# Sheet3.net
KiCad netlist of a schematic drawn in Altium Designer
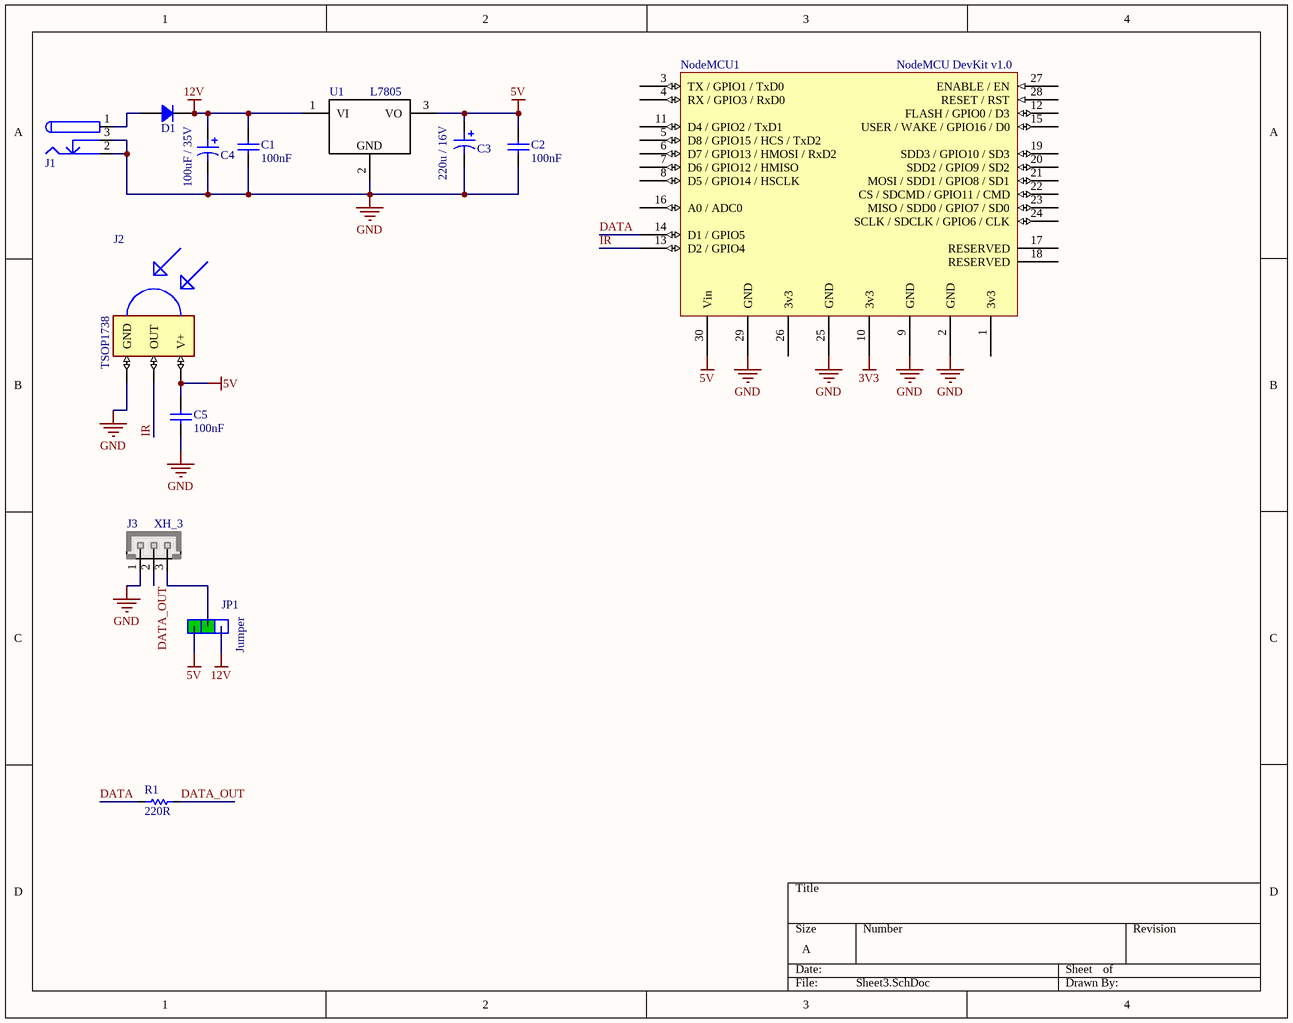
[diagram p0: Sheet3.SchDoc]

(export (version "E")
  (design (tool "Eeschema 10.0.6"))
  (components
    (comp (ref "C1")
      (value "100nF")
      (footprint "CAPC4817X12N")
      (description "CAP 1206")
      (fields (field (name "DESIGNER") "Abbas Basereh"))
      (libsource (lib "4_5924601381297062174") (part "CAP SMD 1206"))
    )
    (comp (ref "C2")
      (value "100nF")
      (footprint "CAPC4817X12N")
      (description "CAP 1206")
      (fields (field (name "DESIGNER") "Abbas Basereh"))
      (libsource (lib "4_5924601381297062174") (part "CAP SMD 1206"))
    )
    (comp (ref "C3")
      (value "220u / 16V")
      (footprint "Cap electrolitic radial 8x12-3.5")
      (description "Cap electrolitic radial")
      (fields (field (name "DESIGNER") "Abbas Basereh"))
      (libsource (lib "4_5924601381297062174") (part "Cap ELECTROLITIC TOTAL SIZE"))
    )
    (comp (ref "C4")
      (value "100uF / 35V")
      (footprint "Cap electrolitic radial 10x20-5")
      (description "Cap electrolitic radial")
      (fields (field (name "DESIGNER") "Abbas Basereh"))
      (libsource (lib "4_5924601381297062174") (part "Cap ELECTROLITIC TOTAL SIZE"))
    )
    (comp (ref "C5")
      (value "100nF")
      (footprint "CAPC4817X12N")
      (description "CAP 1206")
      (fields (field (name "DESIGNER") "Abbas Basereh"))
      (libsource (lib "4_5924601381297062174") (part "CAP SMD 1206"))
    )
    (comp (ref "D1")
      (value "1N4007")
      (footprint "DO41 P7.5MM")
      (description "Diode Standard 1000V 1A Through Hole DO-204AL (DO-41)")
      (libsource (lib "Diode") (part "1N4007 (THD)"))
    )
    (comp (ref "J1")
      (value "DC Power Jack")
      (footprint "DC Power Jack 1")
      (description "DC Power Jack. Center Pin 2.5mm. Diameter: 5.7mm")
      (fields (field (name "DESIGNER") "Ali Hafizi"))
      (libsource (lib "4_5965406465417019807") (part "DC Power Jack"))
    )
    (comp (ref "J2")
      (value "TSOP1738")
      (footprint "TSOP17XX")
      (description "IR Remote Receiver 38KHz 35m 3-Pin")
      (fields (field (name "MP") "TSOP1738.") (field (name "MF") "Vishay"))
      (libsource (lib "TSOP1738") (part "TSOP1738"))
    )
    (comp (ref "J3")
      (value "XH_3")
      (footprint "XH_3")
      (description "PW10-x-M, JST-BxB-XH-A pitch: 2.5mm, 3A/250v")
      (fields (field (name "MANF") "JST") (field (name "MANF_P#") "B3B-XH-A"))
      (libsource (lib "Library_Package") (part "XH_3"))
    )
    (comp (ref "JP1")
      (value "Jumper")
      (footprint "jumper selector")
      (description "Jumper Selector")
      (libsource (lib "4_5965406465417019807") (part "Jumper Selector"))
    )
    (comp (ref "NodeMCU1")
      (value "NodeMCU DevKit v1.0")
      (footprint "NODEMCU")
      (libsource (lib "Personal-Altium-Library-master") (part "NodeMCU DevKit v1.0"))
    )
    (comp (ref "R1")
      (value "220R")
      (footprint "Res-(1/4)")
      (description "Resistor")
      (fields (field (name "TOLERANCE") "5%") (field (name "POWER") "1/4 W"))
      (libsource (lib "AltiumLib1 (1)") (part "Resistor"))
    )
    (comp (ref "U1")
      (value "L7805")
      (footprint "to220-123-v")
      (description "LINEAR REGULATOR 5.0V")
      (libsource (lib "General_05") (part "L7805-TO220"))
    )
  )
  (nets
    (net (code "1") (name "/DATA") (class "Default")
      (node (ref "NodeMCU1") (pin "14") (pinfunction "D1_/_GPIO5_14") (pintype "bidirectional"))
      (node (ref "R1") (pin "1") (pinfunction "1_1") (pintype "passive"))
    )
    (net (code "2") (name "/DATA_OUT") (class "Default")
      (node (ref "J3") (pin "2") (pinfunction "2_2") (pintype "passive"))
      (node (ref "R1") (pin "2") (pinfunction "2_2") (pintype "passive"))
    )
    (net (code "3") (name "/IR") (class "Default")
      (node (ref "J2") (pin "OUT") (pinfunction "OUT_OUT") (pintype "bidirectional"))
      (node (ref "NodeMCU1") (pin "13") (pinfunction "D2_/_GPIO4_13") (pintype "bidirectional"))
    )
    (net (code "4") (name "3V3") (class "Default")
      (node (ref "NodeMCU1") (pin "10") (pinfunction "3v3_10") (pintype "power_in"))
    )
    (net (code "5") (name "5V") (class "Default")
      (node (ref "C2") (pin "1") (pinfunction "1_1") (pintype "passive"))
      (node (ref "C3") (pin "1") (pinfunction "1_1") (pintype "passive"))
      (node (ref "C5") (pin "1") (pinfunction "1_1") (pintype "passive"))
      (node (ref "J2") (pin "V+") (pinfunction "V+_V+") (pintype "bidirectional"))
      (node (ref "JP1") (pin "1") (pinfunction "1_1") (pintype "passive"))
      (node (ref "NodeMCU1") (pin "30") (pinfunction "Vin_30") (pintype "passive"))
      (node (ref "U1") (pin "3") (pinfunction "VO_3") (pintype "passive"))
    )
    (net (code "6") (name "12V") (class "Default")
      (node (ref "C1") (pin "2") (pinfunction "2_2") (pintype "passive"))
      (node (ref "C4") (pin "1") (pinfunction "1_1") (pintype "passive"))
      (node (ref "D1") (pin "2") (pinfunction "2_2") (pintype "passive"))
      (node (ref "JP1") (pin "3") (pinfunction "3_3") (pintype "passive"))
      (node (ref "U1") (pin "1") (pinfunction "VI_1") (pintype "passive"))
    )
    (net (code "7") (name "GND") (class "Default")
      (node (ref "C1") (pin "1") (pinfunction "1_1") (pintype "passive"))
      (node (ref "C2") (pin "2") (pinfunction "2_2") (pintype "passive"))
      (node (ref "C3") (pin "2") (pinfunction "2_2") (pintype "passive"))
      (node (ref "C4") (pin "2") (pinfunction "2_2") (pintype "passive"))
      (node (ref "C5") (pin "2") (pinfunction "2_2") (pintype "passive"))
      (node (ref "J1") (pin "2") (pinfunction "2_2") (pintype "power_in"))
      (node (ref "J1") (pin "3") (pinfunction "3_3") (pintype "power_in"))
      (node (ref "J2") (pin "GND") (pinfunction "GND_GND") (pintype "bidirectional"))
      (node (ref "J3") (pin "1") (pinfunction "1_1") (pintype "passive"))
      (node (ref "NodeMCU1") (pin "2") (pinfunction "GND_2") (pintype "power_in"))
      (node (ref "NodeMCU1") (pin "25") (pinfunction "GND_25") (pintype "power_in"))
      (node (ref "NodeMCU1") (pin "29") (pinfunction "GND_29") (pintype "passive"))
      (node (ref "NodeMCU1") (pin "9") (pinfunction "GND_9") (pintype "power_in"))
      (node (ref "U1") (pin "2") (pintype "passive"))
    )
    (net (code "8") (name "Net-(D1-Pad1)") (class "Default")
      (node (ref "D1") (pin "1") (pinfunction "1_1") (pintype "passive"))
      (node (ref "J1") (pin "1") (pinfunction "1_1") (pintype "power_in"))
    )
    (net (code "9") (name "Net-(J3-Pad3)") (class "Default")
      (node (ref "J3") (pin "3") (pinfunction "3_3") (pintype "passive"))
      (node (ref "JP1") (pin "2") (pinfunction "2_2") (pintype "passive"))
    )
    (net (code "10") (name "unconnected-(NodeMCU1-3v3-Pad1)") (class "Default")
      (node (ref "NodeMCU1") (pin "1") (pinfunction "3v3_1") (pintype "power_in"))
    )
    (net (code "11") (name "unconnected-(NodeMCU1-3v3-Pad26)") (class "Default")
      (node (ref "NodeMCU1") (pin "26") (pinfunction "3v3_26") (pintype "power_in"))
    )
    (net (code "12") (name "unconnected-(NodeMCU1-A0_{slash}_ADC0-Pad16)") (class "Default")
      (node (ref "NodeMCU1") (pin "16") (pinfunction "A0_/_ADC0_16") (pintype "bidirectional"))
    )
    (net (code "13") (name "unconnected-(NodeMCU1-CS_{slash}_SDCMD_{slash}_GPIO11_{slash}_CMD-Pad22)") (class "Default")
      (node (ref "NodeMCU1") (pin "22") (pinfunction "CS_/_SDCMD_/_GPIO11_/_CMD_22") (pintype "bidirectional"))
    )
    (net (code "14") (name "unconnected-(NodeMCU1-D4_{slash}_GPIO2_{slash}_TxD1-Pad11)") (class "Default")
      (node (ref "NodeMCU1") (pin "11") (pinfunction "D4_/_GPIO2_/_TxD1_11") (pintype "bidirectional"))
    )
    (net (code "15") (name "unconnected-(NodeMCU1-D5_{slash}_GPIO14_{slash}_HSCLK-Pad8)") (class "Default")
      (node (ref "NodeMCU1") (pin "8") (pinfunction "D5_/_GPIO14_/_HSCLK_8") (pintype "bidirectional"))
    )
    (net (code "16") (name "unconnected-(NodeMCU1-D6_{slash}_GPIO12_{slash}_HMISO-Pad7)") (class "Default")
      (node (ref "NodeMCU1") (pin "7") (pinfunction "D6_/_GPIO12_/_HMISO_7") (pintype "bidirectional"))
    )
    (net (code "17") (name "unconnected-(NodeMCU1-D7_{slash}_GPIO13_{slash}_HMOSI_{slash}_RxD2-Pad6)") (class "Default")
      (node (ref "NodeMCU1") (pin "6") (pinfunction "D7_/_GPIO13_/_HMOSI_/_RxD2_6") (pintype "bidirectional"))
    )
    (net (code "18") (name "unconnected-(NodeMCU1-D8_{slash}_GPIO15_{slash}_HCS_{slash}_TxD2-Pad5)") (class "Default")
      (node (ref "NodeMCU1") (pin "5") (pinfunction "D8_/_GPIO15_/_HCS_/_TxD2_5") (pintype "bidirectional"))
    )
    (net (code "19") (name "unconnected-(NodeMCU1-ENABLE_{slash}_EN-Pad27)") (class "Default")
      (node (ref "NodeMCU1") (pin "27") (pinfunction "ENABLE_/_EN_27") (pintype "input"))
    )
    (net (code "20") (name "unconnected-(NodeMCU1-FLASH_{slash}_GPIO0_{slash}_D3-Pad12)") (class "Default")
      (node (ref "NodeMCU1") (pin "12") (pinfunction "FLASH_/_GPIO0_/_D3_12") (pintype "bidirectional"))
    )
    (net (code "21") (name "unconnected-(NodeMCU1-MISO_{slash}_SDD0_{slash}_GPIO7_{slash}_SD0-Pad23)") (class "Default")
      (node (ref "NodeMCU1") (pin "23") (pinfunction "MISO_/_SDD0_/_GPIO7_/_SD0_23") (pintype "bidirectional"))
    )
    (net (code "22") (name "unconnected-(NodeMCU1-MOSI_{slash}_SDD1_{slash}_GPIO8_{slash}_SD1-Pad21)") (class "Default")
      (node (ref "NodeMCU1") (pin "21") (pinfunction "MOSI_/_SDD1_/_GPIO8_/_SD1_21") (pintype "bidirectional"))
    )
    (net (code "23") (name "unconnected-(NodeMCU1-RESERVED-Pad17)") (class "Default")
      (node (ref "NodeMCU1") (pin "17") (pinfunction "RESERVED_17") (pintype "passive"))
    )
    (net (code "24") (name "unconnected-(NodeMCU1-RESERVED-Pad18)") (class "Default")
      (node (ref "NodeMCU1") (pin "18") (pinfunction "RESERVED_18") (pintype "passive"))
    )
    (net (code "25") (name "unconnected-(NodeMCU1-RESET_{slash}_RST-Pad28)") (class "Default")
      (node (ref "NodeMCU1") (pin "28") (pinfunction "RESET_/_RST_28") (pintype "input"))
    )
    (net (code "26") (name "unconnected-(NodeMCU1-RX_{slash}_GPIO3_{slash}_RxD0-Pad4)") (class "Default")
      (node (ref "NodeMCU1") (pin "4") (pinfunction "RX_/_GPIO3_/_RxD0_4") (pintype "bidirectional"))
    )
    (net (code "27") (name "unconnected-(NodeMCU1-SCLK_{slash}_SDCLK_{slash}_GPIO6_{slash}_CLK-Pad24)") (class "Default")
      (node (ref "NodeMCU1") (pin "24") (pinfunction "SCLK_/_SDCLK_/_GPIO6_/_CLK_24") (pintype "bidirectional"))
    )
    (net (code "28") (name "unconnected-(NodeMCU1-SDD2_{slash}_GPIO9_{slash}_SD2-Pad20)") (class "Default")
      (node (ref "NodeMCU1") (pin "20") (pinfunction "SDD2_/_GPIO9_/_SD2_20") (pintype "bidirectional"))
    )
    (net (code "29") (name "unconnected-(NodeMCU1-SDD3_{slash}_GPIO10_{slash}_SD3-Pad19)") (class "Default")
      (node (ref "NodeMCU1") (pin "19") (pinfunction "SDD3_/_GPIO10_/_SD3_19") (pintype "bidirectional"))
    )
    (net (code "30") (name "unconnected-(NodeMCU1-TX_{slash}_GPIO1_{slash}_TxD0-Pad3)") (class "Default")
      (node (ref "NodeMCU1") (pin "3") (pinfunction "TX_/_GPIO1_/_TxD0_3") (pintype "bidirectional"))
    )
    (net (code "31") (name "unconnected-(NodeMCU1-USER_{slash}_WAKE_{slash}_GPIO16_{slash}_D0-Pad15)") (class "Default")
      (node (ref "NodeMCU1") (pin "15") (pinfunction "USER_/_WAKE_/_GPIO16_/_D0_15") (pintype "bidirectional"))
    )
  )
)
